# M160C.net
KiCad netlist of a schematic drawn in EAGLE
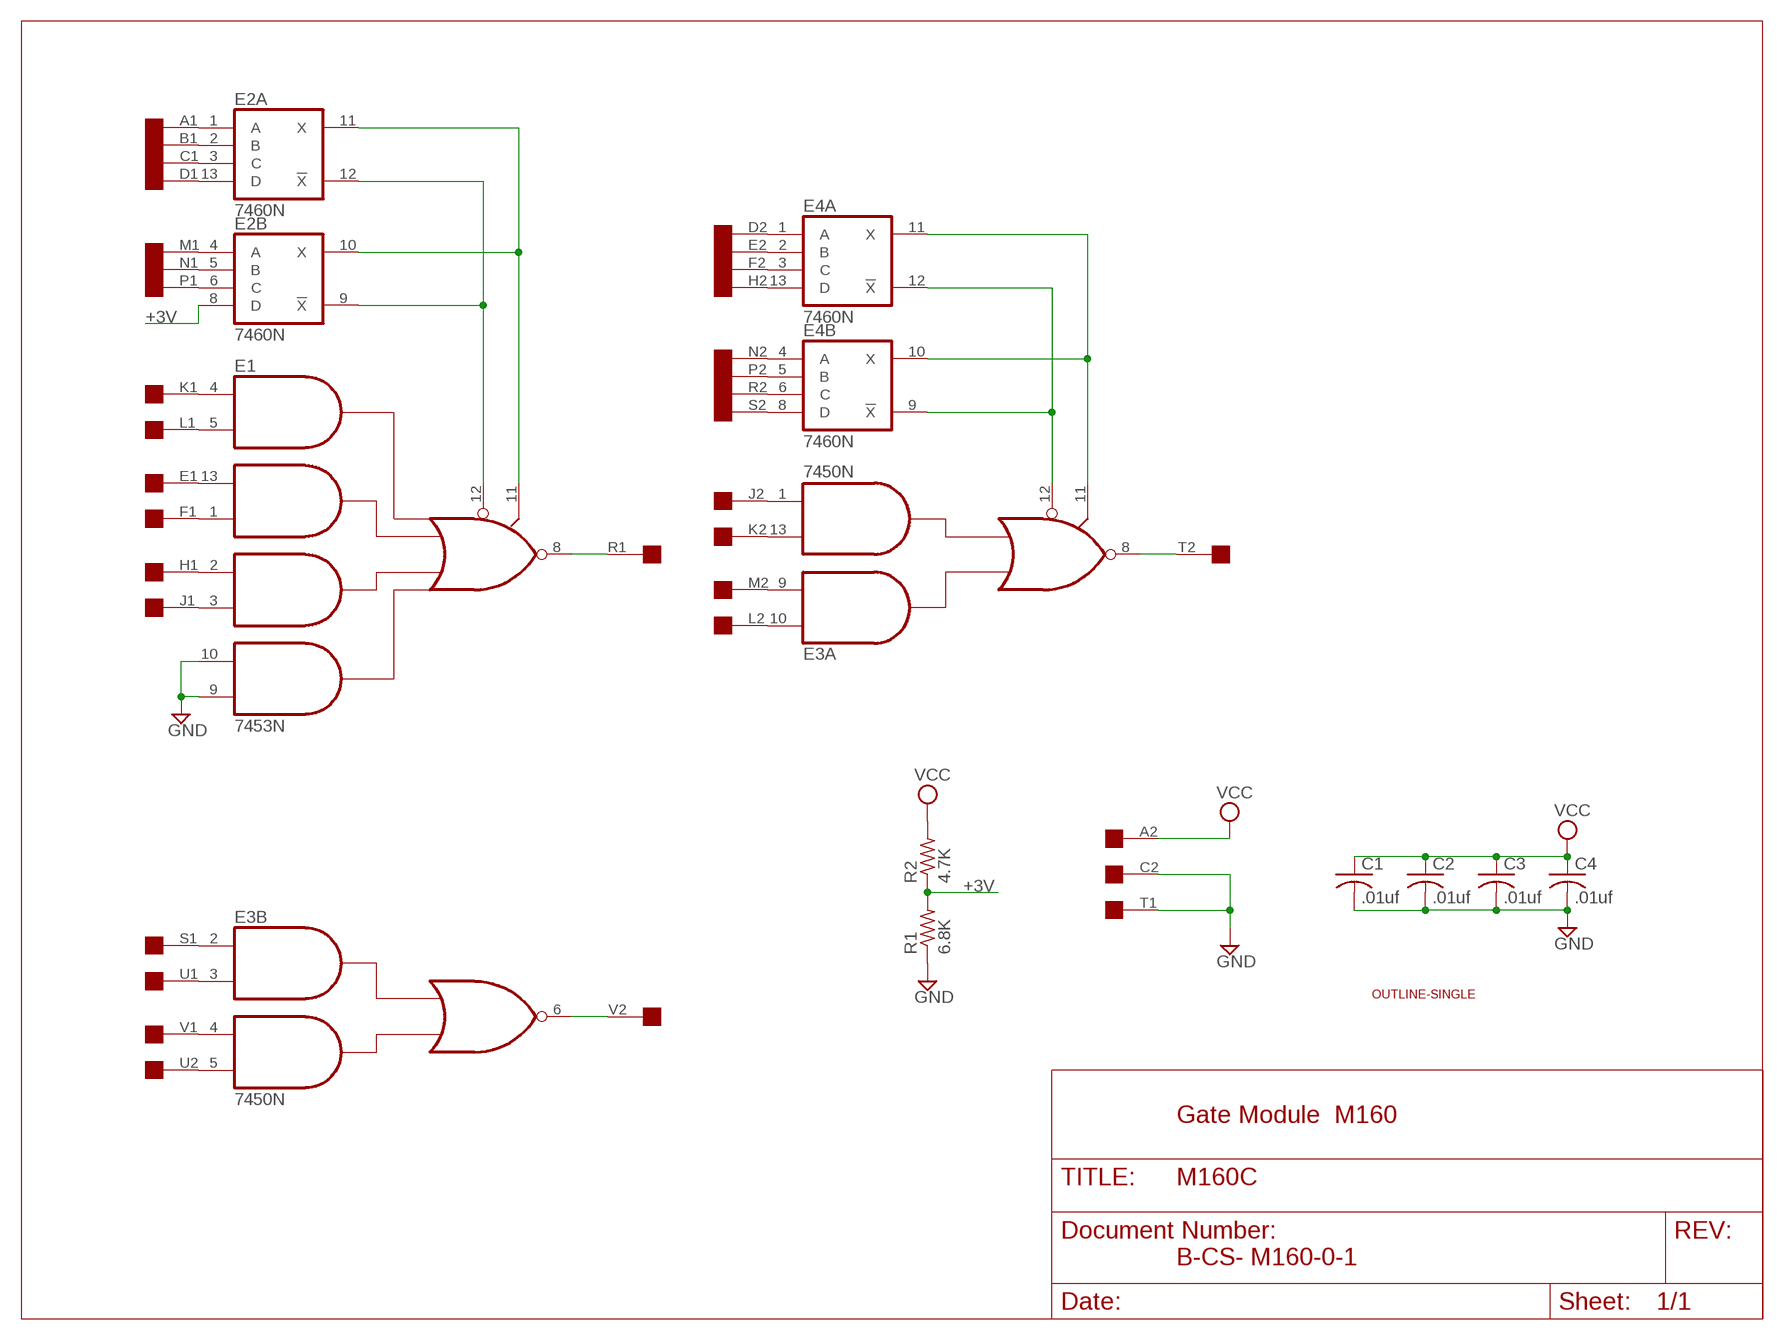
[diagram p0: schematic, sheet 1]

(export (version "E")
  (design (tool "Eeschema 10.0.6"))
  (components
    (comp (ref "C1")
      (value ".01uf")
      (footprint "eagle-import:C050-025X075")
      (libsource (lib "eagle-import") (part "C-US050-025X075"))
    )
    (comp (ref "C2")
      (value ".01uf")
      (footprint "eagle-import:C050-025X075")
      (libsource (lib "eagle-import") (part "C-US050-025X075"))
    )
    (comp (ref "C3")
      (value ".01uf")
      (footprint "eagle-import:C050-025X075")
      (libsource (lib "eagle-import") (part "C-US050-025X075"))
    )
    (comp (ref "C4")
      (value ".01uf")
      (footprint "eagle-import:C050-025X075")
      (libsource (lib "eagle-import") (part "C-US050-025X075"))
    )
    (comp (ref "E1")
      (value "7453N")
      (footprint "eagle-import:DIL14")
      (libsource (lib "eagle-import") (part "7453N"))
    )
    (comp (ref "E2")
      (value "7460N")
      (footprint "eagle-import:DIL14")
      (libsource (lib "eagle-import") (part "7460N"))
    )
    (comp (ref "E3")
      (value "7450N")
      (footprint "eagle-import:DIL14")
      (libsource (lib "eagle-import") (part "7450N"))
    )
    (comp (ref "E4")
      (value "7460N")
      (footprint "eagle-import:DIL14")
      (libsource (lib "eagle-import") (part "7460N"))
    )
    (comp (ref "R1")
      (value "6.8K")
      (footprint "eagle-import:0207_10")
      (libsource (lib "eagle-import") (part "R-US_0207/10"))
    )
    (comp (ref "R2")
      (value "4.7K")
      (footprint "eagle-import:0207_10")
      (libsource (lib "eagle-import") (part "R-US_0207/10"))
    )
    (comp (ref "U$1")
      (value "OUTLINE-SINGLE")
      (footprint "eagle-import:SINGLE")
      (libsource (lib "eagle-import") (part "OUTLINE-SINGLE"))
    )
    (comp (ref "U$4")
      (value "SINGLE")
      (footprint "eagle-import:EDGE-CON2")
      (libsource (lib "eagle-import") (part "SINGLE"))
    )
  )
  (nets
    (net (code "1") (name "/+3V") (class "Default")
      (node (ref "E2") (pin "8") (pinfunction "D_8") (pintype "input"))
      (node (ref "R1") (pin "2") (pinfunction "2_2") (pintype "passive"))
      (node (ref "R2") (pin "1") (pinfunction "1_1") (pintype "passive"))
    )
    (net (code "2") (name "GND") (class "Default")
      (node (ref "C1") (pin "2") (pinfunction "2_2") (pintype "passive"))
      (node (ref "C2") (pin "2") (pinfunction "2_2") (pintype "passive"))
      (node (ref "C3") (pin "2") (pinfunction "2_2") (pintype "passive"))
      (node (ref "C4") (pin "2") (pinfunction "2_2") (pintype "passive"))
      (node (ref "E1") (pin "10") (pinfunction "I7_10") (pintype "input"))
      (node (ref "E1") (pin "9") (pinfunction "I8_9") (pintype "input"))
      (node (ref "R1") (pin "1") (pinfunction "1_1") (pintype "passive"))
      (node (ref "U$4") (pin "C2") (pinfunction "1_C2") (pintype "bidirectional"))
      (node (ref "U$4") (pin "T1") (pinfunction "1_T1") (pintype "bidirectional"))
    )
    (net (code "3") (name "Net-(E1A-I1)") (class "Default")
      (node (ref "E1") (pin "4") (pinfunction "I1_4") (pintype "input"))
      (node (ref "U$4") (pin "K1") (pinfunction "1_K1") (pintype "bidirectional"))
    )
    (net (code "4") (name "Net-(E1A-I2)") (class "Default")
      (node (ref "E1") (pin "5") (pinfunction "I2_5") (pintype "input"))
      (node (ref "U$4") (pin "L1") (pinfunction "1_L1") (pintype "bidirectional"))
    )
    (net (code "5") (name "Net-(E1A-I3)") (class "Default")
      (node (ref "E1") (pin "13") (pinfunction "I3_13") (pintype "input"))
      (node (ref "U$4") (pin "E1") (pinfunction "1_E1") (pintype "bidirectional"))
    )
    (net (code "6") (name "Net-(E1A-I4)") (class "Default")
      (node (ref "E1") (pin "1") (pinfunction "I4_1") (pintype "input"))
      (node (ref "U$4") (pin "F1") (pinfunction "1_F1") (pintype "bidirectional"))
    )
    (net (code "7") (name "Net-(E1A-I5)") (class "Default")
      (node (ref "E1") (pin "2") (pinfunction "I5_2") (pintype "input"))
      (node (ref "U$4") (pin "H1") (pinfunction "1_H1") (pintype "bidirectional"))
    )
    (net (code "8") (name "Net-(E1A-I6)") (class "Default")
      (node (ref "E1") (pin "3") (pinfunction "I6_3") (pintype "input"))
      (node (ref "U$4") (pin "J1") (pinfunction "1_J1") (pintype "bidirectional"))
    )
    (net (code "9") (name "Net-(E1A-I9)") (class "Default")
      (node (ref "E1") (pin "12") (pinfunction "I9_12") (pintype "passive"))
      (node (ref "E2") (pin "12") (pinfunction "~{X}_12") (pintype "output"))
      (node (ref "E2") (pin "9") (pinfunction "~{X}_9") (pintype "output"))
    )
    (net (code "10") (name "Net-(E1A-I10)") (class "Default")
      (node (ref "E1") (pin "11") (pinfunction "I10_11") (pintype "passive"))
      (node (ref "E2") (pin "10") (pinfunction "X_10") (pintype "output"))
      (node (ref "E2") (pin "11") (pinfunction "X_11") (pintype "output"))
    )
    (net (code "11") (name "Net-(E1A-O)") (class "Default")
      (node (ref "E1") (pin "8") (pinfunction "O_8") (pintype "output"))
      (node (ref "U$4") (pin "R1") (pinfunction "1_R1") (pintype "bidirectional"))
    )
    (net (code "12") (name "Net-(E2A-A)") (class "Default")
      (node (ref "E2") (pin "1") (pinfunction "A_1") (pintype "input"))
      (node (ref "U$4") (pin "A1") (pinfunction "1_A1") (pintype "bidirectional"))
    )
    (net (code "13") (name "Net-(E2A-B)") (class "Default")
      (node (ref "E2") (pin "2") (pinfunction "B_2") (pintype "input"))
      (node (ref "U$4") (pin "B1") (pinfunction "1_B1") (pintype "bidirectional"))
    )
    (net (code "14") (name "Net-(E2A-C)") (class "Default")
      (node (ref "E2") (pin "3") (pinfunction "C_3") (pintype "input"))
      (node (ref "U$4") (pin "C1") (pinfunction "1_C1") (pintype "bidirectional"))
    )
    (net (code "15") (name "Net-(E2A-D)") (class "Default")
      (node (ref "E2") (pin "13") (pinfunction "D_13") (pintype "input"))
      (node (ref "U$4") (pin "D1") (pinfunction "1_D1") (pintype "bidirectional"))
    )
    (net (code "16") (name "Net-(E2B-A)") (class "Default")
      (node (ref "E2") (pin "4") (pinfunction "A_4") (pintype "input"))
      (node (ref "U$4") (pin "M1") (pinfunction "1_M1") (pintype "bidirectional"))
    )
    (net (code "17") (name "Net-(E2B-B)") (class "Default")
      (node (ref "E2") (pin "5") (pinfunction "B_5") (pintype "input"))
      (node (ref "U$4") (pin "N1") (pinfunction "1_N1") (pintype "bidirectional"))
    )
    (net (code "18") (name "Net-(E2B-C)") (class "Default")
      (node (ref "E2") (pin "6") (pinfunction "C_6") (pintype "input"))
      (node (ref "U$4") (pin "P1") (pinfunction "1_P1") (pintype "bidirectional"))
    )
    (net (code "19") (name "Net-(E3A-I1)") (class "Default")
      (node (ref "E3") (pin "10") (pinfunction "I1_10") (pintype "input"))
      (node (ref "U$4") (pin "L2") (pinfunction "1_L2") (pintype "bidirectional"))
    )
    (net (code "20") (name "Net-(E3A-I2)") (class "Default")
      (node (ref "E3") (pin "9") (pinfunction "I2_9") (pintype "input"))
      (node (ref "U$4") (pin "M2") (pinfunction "1_M2") (pintype "bidirectional"))
    )
    (net (code "21") (name "Net-(E3A-I3)") (class "Default")
      (node (ref "E3") (pin "13") (pinfunction "I3_13") (pintype "input"))
      (node (ref "U$4") (pin "K2") (pinfunction "1_K2") (pintype "bidirectional"))
    )
    (net (code "22") (name "Net-(E3A-I4)") (class "Default")
      (node (ref "E3") (pin "1") (pinfunction "I4_1") (pintype "input"))
      (node (ref "U$4") (pin "J2") (pinfunction "1_J2") (pintype "bidirectional"))
    )
    (net (code "23") (name "Net-(E3A-I5)") (class "Default")
      (node (ref "E3") (pin "12") (pinfunction "I5_12") (pintype "passive"))
      (node (ref "E4") (pin "12") (pinfunction "~{X}_12") (pintype "output"))
      (node (ref "E4") (pin "9") (pinfunction "~{X}_9") (pintype "output"))
    )
    (net (code "24") (name "Net-(E3A-I6)") (class "Default")
      (node (ref "E3") (pin "11") (pinfunction "I6_11") (pintype "passive"))
      (node (ref "E4") (pin "10") (pinfunction "X_10") (pintype "output"))
      (node (ref "E4") (pin "11") (pinfunction "X_11") (pintype "output"))
    )
    (net (code "25") (name "Net-(E3A-O)") (class "Default")
      (node (ref "E3") (pin "8") (pinfunction "O_8") (pintype "output"))
      (node (ref "U$4") (pin "T2") (pinfunction "1_T2") (pintype "bidirectional"))
    )
    (net (code "26") (name "Net-(E3B-I1)") (class "Default")
      (node (ref "E3") (pin "2") (pinfunction "I1_2") (pintype "input"))
      (node (ref "U$4") (pin "S1") (pinfunction "1_S1") (pintype "bidirectional"))
    )
    (net (code "27") (name "Net-(E3B-I2)") (class "Default")
      (node (ref "E3") (pin "3") (pinfunction "I2_3") (pintype "input"))
      (node (ref "U$4") (pin "U1") (pinfunction "1_U1") (pintype "bidirectional"))
    )
    (net (code "28") (name "Net-(E3B-I3)") (class "Default")
      (node (ref "E3") (pin "4") (pinfunction "I3_4") (pintype "input"))
      (node (ref "U$4") (pin "V1") (pinfunction "1_V1") (pintype "bidirectional"))
    )
    (net (code "29") (name "Net-(E3B-I4)") (class "Default")
      (node (ref "E3") (pin "5") (pinfunction "I4_5") (pintype "input"))
      (node (ref "U$4") (pin "U2") (pinfunction "1_U2") (pintype "bidirectional"))
    )
    (net (code "30") (name "Net-(E3B-O)") (class "Default")
      (node (ref "E3") (pin "6") (pinfunction "O_6") (pintype "output"))
      (node (ref "U$4") (pin "V2") (pinfunction "1_V2") (pintype "bidirectional"))
    )
    (net (code "31") (name "Net-(E4A-A)") (class "Default")
      (node (ref "E4") (pin "1") (pinfunction "A_1") (pintype "input"))
      (node (ref "U$4") (pin "D2") (pinfunction "1_D2") (pintype "bidirectional"))
    )
    (net (code "32") (name "Net-(E4A-B)") (class "Default")
      (node (ref "E4") (pin "2") (pinfunction "B_2") (pintype "input"))
      (node (ref "U$4") (pin "E2") (pinfunction "1_E2") (pintype "bidirectional"))
    )
    (net (code "33") (name "Net-(E4A-C)") (class "Default")
      (node (ref "E4") (pin "3") (pinfunction "C_3") (pintype "input"))
      (node (ref "U$4") (pin "F2") (pinfunction "1_F2") (pintype "bidirectional"))
    )
    (net (code "34") (name "Net-(E4A-D)") (class "Default")
      (node (ref "E4") (pin "13") (pinfunction "D_13") (pintype "input"))
      (node (ref "U$4") (pin "H2") (pinfunction "1_H2") (pintype "bidirectional"))
    )
    (net (code "35") (name "Net-(E4B-A)") (class "Default")
      (node (ref "E4") (pin "4") (pinfunction "A_4") (pintype "input"))
      (node (ref "U$4") (pin "N2") (pinfunction "1_N2") (pintype "bidirectional"))
    )
    (net (code "36") (name "Net-(E4B-B)") (class "Default")
      (node (ref "E4") (pin "5") (pinfunction "B_5") (pintype "input"))
      (node (ref "U$4") (pin "P2") (pinfunction "1_P2") (pintype "bidirectional"))
    )
    (net (code "37") (name "Net-(E4B-C)") (class "Default")
      (node (ref "E4") (pin "6") (pinfunction "C_6") (pintype "input"))
      (node (ref "U$4") (pin "R2") (pinfunction "1_R2") (pintype "bidirectional"))
    )
    (net (code "38") (name "Net-(E4B-D)") (class "Default")
      (node (ref "E4") (pin "8") (pinfunction "D_8") (pintype "input"))
      (node (ref "U$4") (pin "S2") (pinfunction "1_S2") (pintype "bidirectional"))
    )
    (net (code "39") (name "VCC") (class "Default")
      (node (ref "C1") (pin "1") (pinfunction "1_1") (pintype "passive"))
      (node (ref "C2") (pin "1") (pinfunction "1_1") (pintype "passive"))
      (node (ref "C3") (pin "1") (pinfunction "1_1") (pintype "passive"))
      (node (ref "C4") (pin "1") (pinfunction "1_1") (pintype "passive"))
      (node (ref "R2") (pin "2") (pinfunction "2_2") (pintype "passive"))
      (node (ref "U$4") (pin "A2") (pinfunction "1_A2") (pintype "bidirectional"))
    )
  )
)
